# LoraModule.net
KiCad netlist of a schematic drawn in Altium Designer
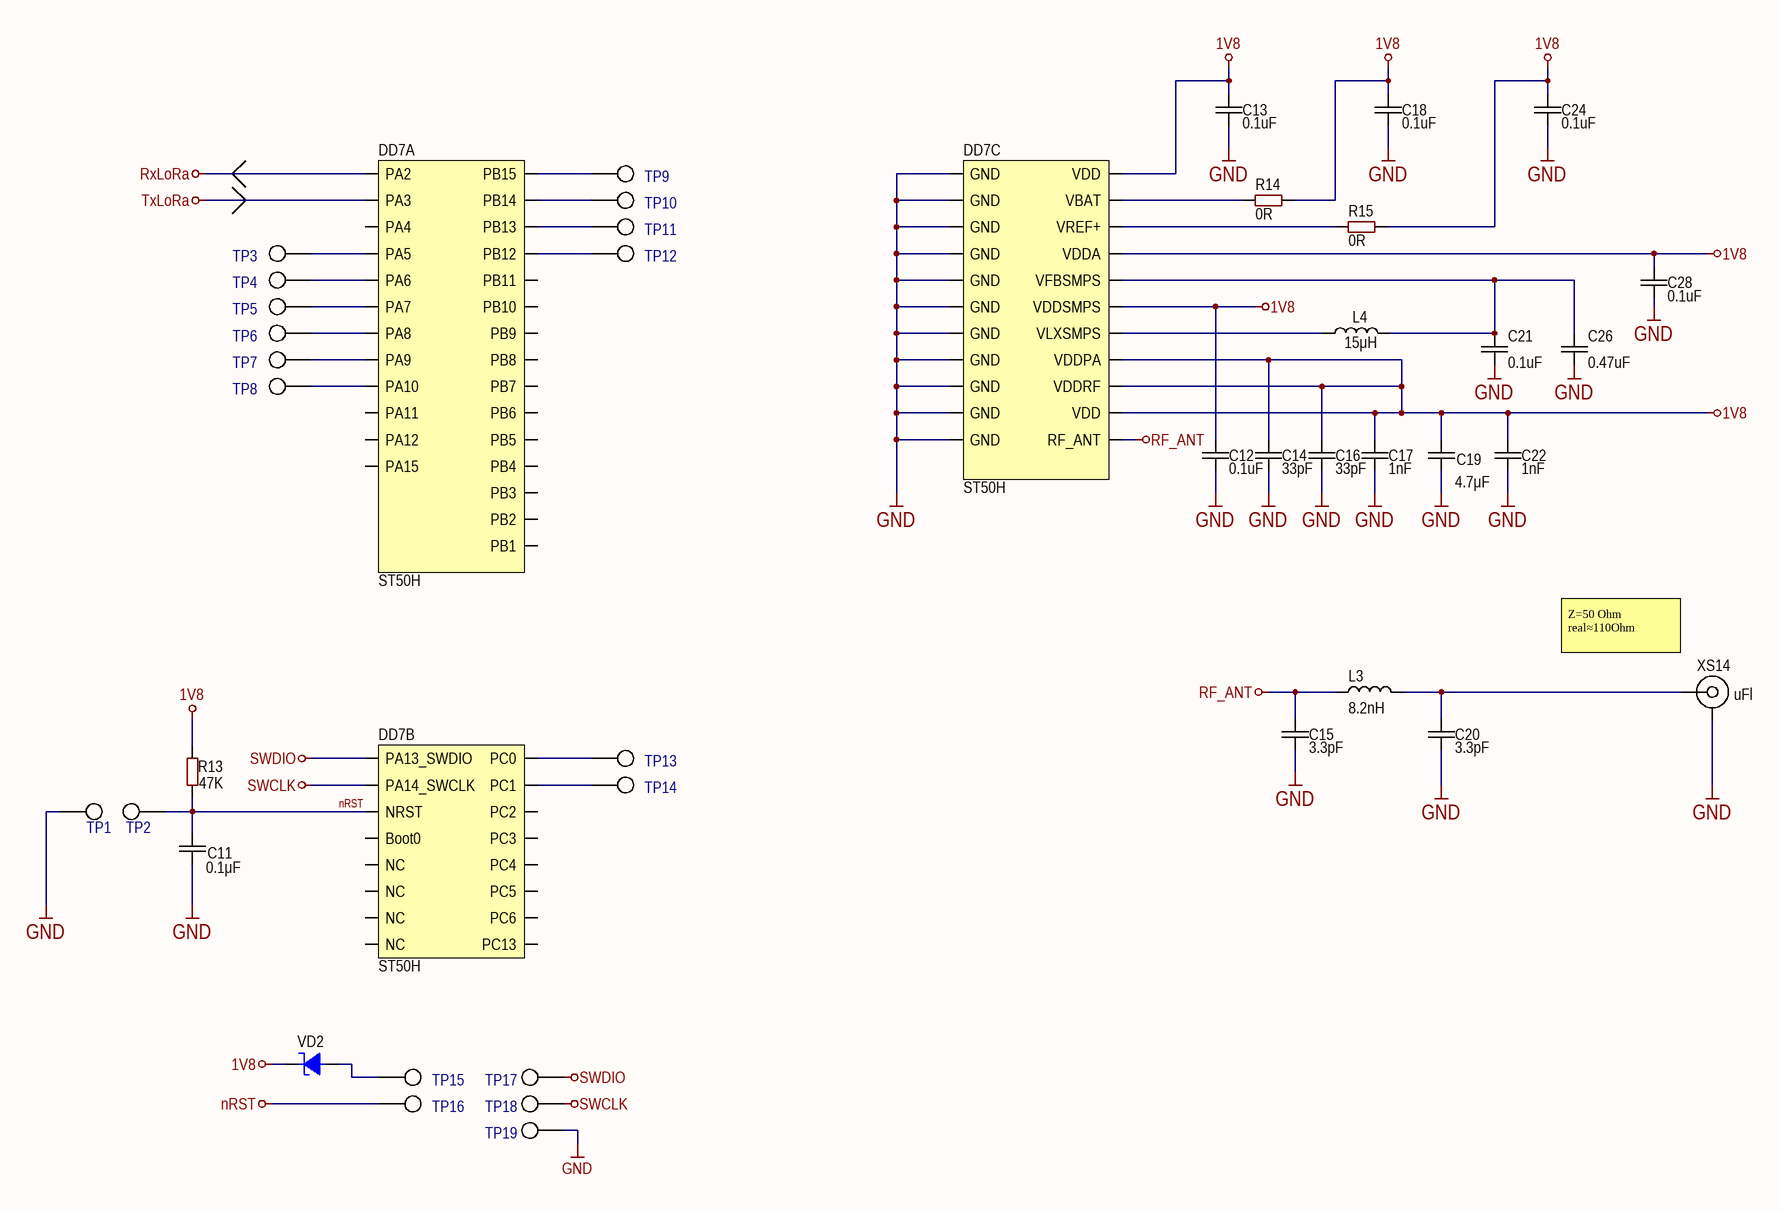
[diagram p0: LoraModule.SchDoc]

(export (version "E")
  (design (tool "Eeschema 10.0.6"))
  (components
    (comp (ref "C11")
      (value "0.1μF")
      (footprint "CAP: 0402")
      (fields
        (field (name "MANUFACTURER") "Yageo")
        (field (name "PARTNUMBER") "CC0402KRX7R7BB104")
        (field (name "VALUEMANUFACTURERPARTNUMBER") "Ceramic capacitor, 0.1μF, X7R, ±10%, 16V, 0402, -55...+125°C")
      )
      (libsource (lib "capacitor") (part "Ceramic_0402"))
    )
    (comp (ref "C12")
      (value "0.1uF")
      (footprint "CAP: 0402")
      (fields
        (field (name "MANUFACTURER") "Yageo")
        (field (name "PARTNUMBER") "CC0402KRX7R7BB104")
        (field (name "VALUEMANUFACTURERPARTNUMBER") "Ceramic capacitor, 0.1uF, X7R, ±10%, 16V, 0402, -55...+125°C")
      )
      (libsource (lib "capacitor") (part "Ceramic_0402"))
    )
    (comp (ref "C13")
      (value "0.1uF")
      (footprint "CAP: 0402")
      (fields
        (field (name "MANUFACTURER") "Yageo")
        (field (name "PARTNUMBER") "CC0402KRX7R7BB104")
        (field (name "VALUEMANUFACTURERPARTNUMBER") "Ceramic capacitor, 0.1uF, X7R, ±10%, 16V, 0402, -55...+125°C")
      )
      (libsource (lib "capacitor") (part "Ceramic_0402"))
    )
    (comp (ref "C14")
      (value "33pF")
      (footprint "CAP: 0402")
      (fields
        (field (name "MANUFACTURER") "Yageo")
        (field (name "PARTNUMBER") "CC0402KRX7R7BB104")
        (field (name "VALUEMANUFACTURERPARTNUMBER") "Ceramic capacitor, 33pF, X7R, ±10%, 16V, 0402, -55...+125°C")
      )
      (libsource (lib "capacitor") (part "Ceramic_0402"))
    )
    (comp (ref "C15")
      (value "3.3pF")
      (footprint "CAP: 0402")
      (fields
        (field (name "MANUFACTURER") "Yageo")
        (field (name "PARTNUMBER") "CC0402KRX7R7BB104")
        (field (name "VALUEMANUFACTURERPARTNUMBER") "Ceramic capacitor, 3.3pF, X7R, ±10%, 16V, 0402, -55...+125°C")
      )
      (libsource (lib "capacitor") (part "Ceramic_0402"))
    )
    (comp (ref "C16")
      (value "33pF")
      (footprint "CAP: 0402")
      (fields
        (field (name "MANUFACTURER") "Yageo")
        (field (name "PARTNUMBER") "CC0402KRX7R7BB104")
        (field (name "VALUEMANUFACTURERPARTNUMBER") "Ceramic capacitor, 33pF, X7R, ±10%, 16V, 0402, -55...+125°C")
      )
      (libsource (lib "capacitor") (part "Ceramic_0402"))
    )
    (comp (ref "C17")
      (value "1nF")
      (footprint "CAP: 0402")
      (fields
        (field (name "MANUFACTURER") "Yageo")
        (field (name "PARTNUMBER") "CC0402KRX7R7BB104")
        (field (name "VALUEMANUFACTURERPARTNUMBER") "Ceramic capacitor, 1nF, X7R, ±10%, 16V, 0402, -55...+125°C")
      )
      (libsource (lib "capacitor") (part "Ceramic_0402"))
    )
    (comp (ref "C18")
      (value "0.1uF")
      (footprint "CAP: 0402")
      (fields
        (field (name "MANUFACTURER") "Yageo")
        (field (name "PARTNUMBER") "CC0402KRX7R7BB104")
        (field (name "VALUEMANUFACTURERPARTNUMBER") "Ceramic capacitor, 0.1uF, X7R, ±10%, 16V, 0402, -55...+125°C")
      )
      (libsource (lib "capacitor") (part "Ceramic_0402"))
    )
    (comp (ref "C19")
      (value "4.7μF")
      (footprint "CAP: 0603")
      (fields
        (field (name "MANUFACTURER") "Yageo")
        (field (name "PARTNUMBER") "CC0603KRX7R7BB104")
        (field (name "VALUEMANUFACTURERPARTNUMBER") "Ceramic capacitor, 4.7μF, X7R, ±10%, 16V, 0603, -55...+125°C")
      )
      (libsource (lib "capacitor") (part "Ceramic_0603"))
    )
    (comp (ref "C20")
      (value "3.3pF")
      (footprint "CAP: 0402")
      (fields
        (field (name "MANUFACTURER") "Yageo")
        (field (name "PARTNUMBER") "CC0402KRX7R7BB104")
        (field (name "VALUEMANUFACTURERPARTNUMBER") "Ceramic capacitor, 3.3pF, X7R, ±10%, 16V, 0402, -55...+125°C")
      )
      (libsource (lib "capacitor") (part "Ceramic_0402"))
    )
    (comp (ref "C21")
      (value "0.1uF")
      (footprint "CAP: 0402")
      (fields
        (field (name "MANUFACTURER") "Yageo")
        (field (name "PARTNUMBER") "CC0402KRX7R7BB104")
        (field (name "VALUEMANUFACTURERPARTNUMBER") "Ceramic capacitor, 0.1uF, X7R, ±10%, 16V, 0402, -55...+125°C")
      )
      (libsource (lib "capacitor") (part "Ceramic_0402"))
    )
    (comp (ref "C22")
      (value "1nF")
      (footprint "CAP: 0402")
      (fields
        (field (name "MANUFACTURER") "Yageo")
        (field (name "PARTNUMBER") "CC0402KRX7R7BB104")
        (field (name "VALUEMANUFACTURERPARTNUMBER") "Ceramic capacitor, 1nF, X7R, ±10%, 16V, 0402, -55...+125°C")
      )
      (libsource (lib "capacitor") (part "Ceramic_0402"))
    )
    (comp (ref "C24")
      (value "0.1uF")
      (footprint "CAP: 0402")
      (fields
        (field (name "MANUFACTURER") "Yageo")
        (field (name "PARTNUMBER") "CC0402KRX7R7BB104")
        (field (name "VALUEMANUFACTURERPARTNUMBER") "Ceramic capacitor, 0.1uF, X7R, ±10%, 16V, 0402, -55...+125°C")
      )
      (libsource (lib "capacitor") (part "Ceramic_0402"))
    )
    (comp (ref "C26")
      (value "0.47uF")
      (footprint "CAP: 0402")
      (fields
        (field (name "MANUFACTURER") "Yageo")
        (field (name "PARTNUMBER") "CC0402KRX7R7BB104")
        (field (name "VALUEMANUFACTURERPARTNUMBER") "Ceramic capacitor, 0.47uF, X7R, ±10%, 16V, 0402, -55...+125°C")
      )
      (libsource (lib "capacitor") (part "Ceramic_0402"))
    )
    (comp (ref "C28")
      (value "0.1uF")
      (footprint "CAP: 0402")
      (fields
        (field (name "MANUFACTURER") "Yageo")
        (field (name "PARTNUMBER") "CC0402KRX7R7BB104")
        (field (name "VALUEMANUFACTURERPARTNUMBER") "Ceramic capacitor, 0.1uF, X7R, ±10%, 16V, 0402, -55...+125°C")
      )
      (libsource (lib "capacitor") (part "Ceramic_0402"))
    )
    (comp (ref "DD7")
      (value "ST50H")
      (footprint "ST50H")
      (description "LoRa module")
      (libsource (lib "ic-rf-transceiver") (part "ST50H"))
    )
    (comp (ref "L3")
      (value "8.2nH")
      (footprint "IND: 0402")
      (fields
        (field (name "MANUFACTURER") "Murata Electronics")
        (field (name "PARTNUMBER") "LQG15HSR10J02D")
        (field (name "VALUEMANUFACTURERPARTNUMBER") "Fixed inductor, 8.2nH, ±5%, 0402, 200mA, -55...+125°C")
      )
      (libsource (lib "inductor") (part "Inductor_0402"))
    )
    (comp (ref "L4")
      (value "15μH")
      (footprint "IND: 0805")
      (fields
        (field (name "MANUFACTURER") "Murata Electronics")
        (field (name "PARTNUMBER") "LQM21FN100M70L")
        (field (name "VALUEMANUFACTURERPARTNUMBER") "Fixed inductor, 15μH, ±20%, 0805, 100mA, -55...+125°C")
      )
      (libsource (lib "inductor") (part "Inductor_0805"))
    )
    (comp (ref "R13")
      (value "47K")
      (footprint "RES: 0402")
      (fields
        (field (name "MANUFACTURER") "Yageo")
        (field (name "PARTNUMBER") "RC0402JR-07100RL")
        (field (name "VALUEMANUFACTURERPARTNUMBER") "Resistor film, 47K, ±5%, 0402, 0.063W, -55...+125°C")
      )
      (libsource (lib "") (part "Resistor_0402_1"))
    )
    (comp (ref "R14")
      (value "0R")
      (footprint "RES: 0402")
      (fields
        (field (name "MANUFACTURER") "Yageo")
        (field (name "PARTNUMBER") "RC0402JR-07100RL")
        (field (name "VALUEMANUFACTURERPARTNUMBER") "Resistor film, 0R, ±5%, 0402, 0.063W, -55...+125°C")
      )
      (libsource (lib "resistor") (part "Resistor_0402"))
    )
    (comp (ref "R15")
      (value "0R")
      (footprint "RES: 0402")
      (fields
        (field (name "MANUFACTURER") "Yageo")
        (field (name "PARTNUMBER") "RC0402JR-07100RL")
        (field (name "VALUEMANUFACTURERPARTNUMBER") "Resistor film, 0R, ±5%, 0402, 0.063W, -55...+125°C")
      )
      (libsource (lib "resistor") (part "Resistor_0402"))
    )
    (comp (ref "TP1")
      (value "Testpoint_HS1mm")
      (footprint "TestPoint(without 3D)")
      (libsource (lib "connector") (part "Testpoint_HS1mm"))
    )
    (comp (ref "TP2")
      (value "Testpoint_HS1mm")
      (footprint "TestPoint(without 3D)")
      (libsource (lib "connector") (part "Testpoint_HS1mm"))
    )
    (comp (ref "TP3")
      (value "Testpoint_HS1mm")
      (footprint "TestPoint(without hole)")
      (libsource (lib "connector") (part "Testpoint_HS1mm"))
    )
    (comp (ref "TP4")
      (value "Testpoint_HS1mm")
      (footprint "TestPoint(without hole)")
      (libsource (lib "connector") (part "Testpoint_HS1mm"))
    )
    (comp (ref "TP5")
      (value "Testpoint_HS1mm")
      (footprint "TestPoint(without hole)")
      (libsource (lib "connector") (part "Testpoint_HS1mm"))
    )
    (comp (ref "TP6")
      (value "Testpoint_HS1mm")
      (footprint "TestPoint(without hole)")
      (libsource (lib "connector") (part "Testpoint_HS1mm"))
    )
    (comp (ref "TP7")
      (value "Testpoint_HS1mm")
      (footprint "TestPoint(without hole)")
      (libsource (lib "connector") (part "Testpoint_HS1mm"))
    )
    (comp (ref "TP8")
      (value "Testpoint_HS1mm")
      (footprint "TestPoint(without hole)")
      (libsource (lib "connector") (part "Testpoint_HS1mm"))
    )
    (comp (ref "TP9")
      (value "Testpoint_HS1mm")
      (footprint "TestPoint(without hole)")
      (libsource (lib "connector") (part "Testpoint_HS1mm"))
    )
    (comp (ref "TP10")
      (value "Testpoint_HS1mm")
      (footprint "TestPoint(without hole)")
      (libsource (lib "connector") (part "Testpoint_HS1mm"))
    )
    (comp (ref "TP11")
      (value "Testpoint_HS1mm")
      (footprint "TestPoint(without hole)")
      (libsource (lib "connector") (part "Testpoint_HS1mm"))
    )
    (comp (ref "TP12")
      (value "Testpoint_HS1mm")
      (footprint "TestPoint(without hole)")
      (libsource (lib "connector") (part "Testpoint_HS1mm"))
    )
    (comp (ref "TP13")
      (value "Testpoint_HS1mm")
      (footprint "TestPoint(without hole)")
      (libsource (lib "connector") (part "Testpoint_HS1mm"))
    )
    (comp (ref "TP14")
      (value "Testpoint_HS1mm")
      (footprint "TestPoint(without hole)")
      (libsource (lib "connector") (part "Testpoint_HS1mm"))
    )
    (comp (ref "TP15")
      (value "Testpoint_HS1mm")
      (footprint "TestPoint(without hole)")
      (libsource (lib "connector") (part "Testpoint_HS1mm"))
    )
    (comp (ref "TP16")
      (value "Testpoint_HS1mm")
      (footprint "TestPoint(without hole)")
      (libsource (lib "connector") (part "Testpoint_HS1mm"))
    )
    (comp (ref "TP17")
      (value "Testpoint_HS1mm")
      (footprint "TestPoint(without hole)")
      (libsource (lib "connector") (part "Testpoint_HS1mm"))
    )
    (comp (ref "TP18")
      (value "Testpoint_HS1mm")
      (footprint "TestPoint(without hole)")
      (libsource (lib "connector") (part "Testpoint_HS1mm"))
    )
    (comp (ref "TP19")
      (value "Testpoint_HS1mm")
      (footprint "TestPoint(without hole)")
      (libsource (lib "connector") (part "Testpoint_HS1mm"))
    )
    (comp (ref "VD2")
      (value "~")
      (footprint "DIODE: SOD523")
      (fields
        (field (name "MANUFACTURER") "Diodes Incorporated")
        (field (name "VALUEMANUFACTURERPARTNUMBER") "Schottky diode, 80V, 500mA, 1V, 15pF, SOD-123, -55...+150°C")
        (field (name "VOLTAGE") "80V")
      )
      (libsource (lib "diode") (part "Schottky_single"))
    )
    (comp (ref "XS14")
      (value "~")
      (footprint "CON: u.Fl")
      (fields
        (field (name "MANUFACTURER") "Hirose Electric")
        (field (name "VALUEMANUFACTURERPARTNUMBER") "Connector u.FL, 50 Ohm, 6GHz")
        (field (name "PARTNUMBER") "U.FL-R-SMT(01)")
        (field (name "COMMENTTEXT") "uFl")
      )
      (libsource (lib "connector") (part "Connector_uFL"))
    )
  )
  (nets
    (net (code "1") (name "1V8") (class "Default")
      (node (ref "C12") (pin "2") (pinfunction "2_2") (pintype "passive"))
      (node (ref "C13") (pin "2") (pinfunction "2_2") (pintype "passive"))
      (node (ref "C14") (pin "2") (pinfunction "2_2") (pintype "passive"))
      (node (ref "C16") (pin "2") (pinfunction "2_2") (pintype "passive"))
      (node (ref "C17") (pin "2") (pinfunction "2_2") (pintype "passive"))
      (node (ref "C18") (pin "2") (pinfunction "2_2") (pintype "passive"))
      (node (ref "C19") (pin "2") (pinfunction "2_2") (pintype "passive"))
      (node (ref "C22") (pin "2") (pinfunction "2_2") (pintype "passive"))
      (node (ref "C24") (pin "2") (pinfunction "2_2") (pintype "passive"))
      (node (ref "C28") (pin "2") (pinfunction "2_2") (pintype "passive"))
      (node (ref "DD7") (pin "11") (pinfunction "VDDSMPS_11") (pintype "passive"))
      (node (ref "DD7") (pin "3") (pinfunction "VDD_3") (pintype "passive"))
      (node (ref "DD7") (pin "53") (pinfunction "VDDPA_53") (pintype "passive"))
      (node (ref "DD7") (pin "54") (pinfunction "VDDRF_54") (pintype "passive"))
      (node (ref "DD7") (pin "55") (pinfunction "VDD_55") (pintype "passive"))
      (node (ref "DD7") (pin "7") (pinfunction "VDDA_7") (pintype "passive"))
      (node (ref "R13") (pin "2") (pinfunction "2_2") (pintype "passive"))
      (node (ref "R14") (pin "1") (pinfunction "1_1") (pintype "passive"))
      (node (ref "R15") (pin "1") (pinfunction "1_1") (pintype "passive"))
      (node (ref "VD2") (pin "2") (pinfunction "2_2") (pintype "passive"))
    )
    (net (code "2") (name "GND") (class "Default")
      (node (ref "C11") (pin "1") (pinfunction "1_1") (pintype "passive"))
      (node (ref "C12") (pin "1") (pinfunction "1_1") (pintype "passive"))
      (node (ref "C13") (pin "1") (pinfunction "1_1") (pintype "passive"))
      (node (ref "C14") (pin "1") (pinfunction "1_1") (pintype "passive"))
      (node (ref "C15") (pin "1") (pinfunction "1_1") (pintype "passive"))
      (node (ref "C16") (pin "1") (pinfunction "1_1") (pintype "passive"))
      (node (ref "C17") (pin "1") (pinfunction "1_1") (pintype "passive"))
      (node (ref "C18") (pin "1") (pinfunction "1_1") (pintype "passive"))
      (node (ref "C19") (pin "1") (pinfunction "1_1") (pintype "passive"))
      (node (ref "C20") (pin "1") (pinfunction "1_1") (pintype "passive"))
      (node (ref "C21") (pin "1") (pinfunction "1_1") (pintype "passive"))
      (node (ref "C22") (pin "1") (pinfunction "1_1") (pintype "passive"))
      (node (ref "C24") (pin "1") (pinfunction "1_1") (pintype "passive"))
      (node (ref "C26") (pin "2") (pinfunction "2_2") (pintype "passive"))
      (node (ref "C28") (pin "1") (pinfunction "1_1") (pintype "passive"))
      (node (ref "DD7") (pin "12") (pinfunction "GND_12") (pintype "passive"))
      (node (ref "DD7") (pin "28") (pinfunction "GND_28") (pintype "passive"))
      (node (ref "DD7") (pin "35") (pinfunction "GND_35") (pintype "passive"))
      (node (ref "DD7") (pin "36") (pinfunction "GND_36") (pintype "passive"))
      (node (ref "DD7") (pin "38") (pinfunction "GND_38") (pintype "passive"))
      (node (ref "DD7") (pin "39") (pinfunction "GND_39") (pintype "passive"))
      (node (ref "DD7") (pin "46") (pinfunction "GND_46") (pintype "passive"))
      (node (ref "DD7") (pin "47") (pinfunction "GND_47") (pintype "passive"))
      (node (ref "DD7") (pin "52") (pinfunction "GND_52") (pintype "passive"))
      (node (ref "DD7") (pin "56") (pinfunction "GND_56") (pintype "passive"))
      (node (ref "DD7") (pin "65") (pinfunction "GND_65") (pintype "passive"))
      (node (ref "TP1") (pin "1") (pinfunction "1_1") (pintype "passive"))
      (node (ref "TP19") (pin "1") (pinfunction "1_1") (pintype "passive"))
      (node (ref "XS14") (pin "2") (pinfunction "2_2") (pintype "passive"))
    )
    (net (code "3") (name "Net-(C20-Pad2)") (class "Default")
      (node (ref "C20") (pin "2") (pinfunction "2_2") (pintype "passive"))
      (node (ref "L3") (pin "2") (pinfunction "2_2") (pintype "passive"))
      (node (ref "XS14") (pin "1") (pinfunction "1_1") (pintype "passive"))
    )
    (net (code "4") (name "Net-(DD7A-PA5)") (class "Default")
      (node (ref "DD7") (pin "32") (pinfunction "PA5_32") (pintype "passive"))
      (node (ref "TP3") (pin "1") (pinfunction "1_1") (pintype "passive"))
    )
    (net (code "5") (name "Net-(DD7A-PA6)") (class "Default")
      (node (ref "DD7") (pin "33") (pinfunction "PA6_33") (pintype "passive"))
      (node (ref "TP4") (pin "1") (pinfunction "1_1") (pintype "passive"))
    )
    (net (code "6") (name "Net-(DD7A-PA7)") (class "Default")
      (node (ref "DD7") (pin "34") (pinfunction "PA7_34") (pintype "passive"))
      (node (ref "TP5") (pin "1") (pinfunction "1_1") (pintype "passive"))
    )
    (net (code "7") (name "Net-(DD7A-PA8)") (class "Default")
      (node (ref "DD7") (pin "51") (pinfunction "PA8_51") (pintype "passive"))
      (node (ref "TP6") (pin "1") (pinfunction "1_1") (pintype "passive"))
    )
    (net (code "8") (name "Net-(DD7A-PA9)") (class "Default")
      (node (ref "DD7") (pin "50") (pinfunction "PA9_50") (pintype "passive"))
      (node (ref "TP7") (pin "1") (pinfunction "1_1") (pintype "passive"))
    )
    (net (code "9") (name "Net-(DD7A-PA10)") (class "Default")
      (node (ref "DD7") (pin "62") (pinfunction "PA10_62") (pintype "passive"))
      (node (ref "TP8") (pin "1") (pinfunction "1_1") (pintype "passive"))
    )
    (net (code "10") (name "Net-(DD7A-PB12)") (class "Default")
      (node (ref "DD7") (pin "59") (pinfunction "PB12_59") (pintype "passive"))
      (node (ref "TP12") (pin "1") (pinfunction "1_1") (pintype "passive"))
    )
    (net (code "11") (name "Net-(DD7A-PB13)") (class "Default")
      (node (ref "DD7") (pin "60") (pinfunction "PB13_60") (pintype "passive"))
      (node (ref "TP11") (pin "1") (pinfunction "1_1") (pintype "passive"))
    )
    (net (code "12") (name "Net-(DD7A-PB14)") (class "Default")
      (node (ref "DD7") (pin "61") (pinfunction "PB14_61") (pintype "passive"))
      (node (ref "TP10") (pin "1") (pinfunction "1_1") (pintype "passive"))
    )
    (net (code "13") (name "Net-(DD7A-PB15)") (class "Default")
      (node (ref "DD7") (pin "9") (pinfunction "PB15_9") (pintype "passive"))
      (node (ref "TP9") (pin "1") (pinfunction "1_1") (pintype "passive"))
    )
    (net (code "14") (name "Net-(DD7B-PC0)") (class "Default")
      (node (ref "DD7") (pin "21") (pinfunction "PC0_21") (pintype "passive"))
      (node (ref "TP13") (pin "1") (pinfunction "1_1") (pintype "passive"))
    )
    (net (code "15") (name "Net-(DD7B-PC1)") (class "Default")
      (node (ref "DD7") (pin "22") (pinfunction "PC1_22") (pintype "passive"))
      (node (ref "TP14") (pin "1") (pinfunction "1_1") (pintype "passive"))
    )
    (net (code "16") (name "Net-(DD7C-VBAT)") (class "Default")
      (node (ref "DD7") (pin "4") (pinfunction "VBAT_4") (pintype "passive"))
      (node (ref "R14") (pin "2") (pinfunction "2_2") (pintype "passive"))
    )
    (net (code "17") (name "Net-(DD7C-VFBSMPS)") (class "Default")
      (node (ref "C21") (pin "2") (pinfunction "2_2") (pintype "passive"))
      (node (ref "C26") (pin "1") (pinfunction "1_1") (pintype "passive"))
      (node (ref "DD7") (pin "10") (pinfunction "VFBSMPS_10") (pintype "passive"))
      (node (ref "L4") (pin "2") (pinfunction "2_2") (pintype "passive"))
    )
    (net (code "18") (name "Net-(DD7C-VLXSMPS)") (class "Default")
      (node (ref "DD7") (pin "13") (pinfunction "VLXSMPS_13") (pintype "passive"))
      (node (ref "L4") (pin "1") (pinfunction "1_1") (pintype "passive"))
    )
    (net (code "19") (name "Net-(DD7C-VREF+)") (class "Default")
      (node (ref "DD7") (pin "6") (pinfunction "VREF+_6") (pintype "passive"))
      (node (ref "R15") (pin "2") (pinfunction "2_2") (pintype "passive"))
    )
    (net (code "20") (name "Net-(TP15-Pad1)") (class "Default")
      (node (ref "TP15") (pin "1") (pinfunction "1_1") (pintype "passive"))
      (node (ref "VD2") (pin "1") (pinfunction "1_1") (pintype "passive"))
    )
    (net (code "21") (name "RF_ANT") (class "Default")
      (node (ref "C15") (pin "2") (pinfunction "2_2") (pintype "passive"))
      (node (ref "DD7") (pin "37") (pinfunction "RF_ANT_37") (pintype "passive"))
      (node (ref "L3") (pin "1") (pinfunction "1_1") (pintype "passive"))
    )
    (net (code "22") (name "RxLoRa") (class "Default")
      (node (ref "DD7") (pin "29") (pinfunction "PA2_29") (pintype "passive"))
    )
    (net (code "23") (name "SWCLK") (class "Default")
      (node (ref "DD7") (pin "2") (pinfunction "PA14_SWCLK_2") (pintype "passive"))
      (node (ref "TP18") (pin "1") (pinfunction "1_1") (pintype "passive"))
    )
    (net (code "24") (name "SWDIO") (class "Default")
      (node (ref "DD7") (pin "1") (pinfunction "PA13_SWDIO_1") (pintype "passive"))
      (node (ref "TP17") (pin "1") (pinfunction "1_1") (pintype "passive"))
    )
    (net (code "25") (name "TxLoRa") (class "Default")
      (node (ref "DD7") (pin "30") (pinfunction "PA3_30") (pintype "passive"))
    )
    (net (code "26") (name "nRST") (class "Default")
      (node (ref "C11") (pin "2") (pinfunction "2_2") (pintype "passive"))
      (node (ref "DD7") (pin "44") (pinfunction "NRST_44") (pintype "passive"))
      (node (ref "R13") (pin "1") (pinfunction "1_1") (pintype "passive"))
      (node (ref "TP16") (pin "1") (pinfunction "1_1") (pintype "passive"))
      (node (ref "TP2") (pin "1") (pinfunction "1_1") (pintype "passive"))
    )
    (net (code "27") (name "unconnected-(DD7A-PA4-Pad31)") (class "Default")
      (node (ref "DD7") (pin "31") (pinfunction "PA4_31") (pintype "passive"))
    )
    (net (code "28") (name "unconnected-(DD7A-PA11-Pad63)") (class "Default")
      (node (ref "DD7") (pin "63") (pinfunction "PA11_63") (pintype "passive"))
    )
    (net (code "29") (name "unconnected-(DD7A-PA12-Pad64)") (class "Default")
      (node (ref "DD7") (pin "64") (pinfunction "PA12_64") (pintype "passive"))
    )
    (net (code "30") (name "unconnected-(DD7A-PA15-Pad8)") (class "Default")
      (node (ref "DD7") (pin "8") (pinfunction "PA15_8") (pintype "passive"))
    )
    (net (code "31") (name "unconnected-(DD7A-PB1-Pad57)") (class "Default")
      (node (ref "DD7") (pin "57") (pinfunction "PB1_57") (pintype "passive"))
    )
    (net (code "32") (name "unconnected-(DD7A-PB2-Pad58)") (class "Default")
      (node (ref "DD7") (pin "58") (pinfunction "PB2_58") (pintype "passive"))
    )
    (net (code "33") (name "unconnected-(DD7A-PB3-Pad14)") (class "Default")
      (node (ref "DD7") (pin "14") (pinfunction "PB3_14") (pintype "passive"))
    )
    (net (code "34") (name "unconnected-(DD7A-PB4-Pad15)") (class "Default")
      (node (ref "DD7") (pin "15") (pinfunction "PB4_15") (pintype "passive"))
    )
    (net (code "35") (name "unconnected-(DD7A-PB5-Pad16)") (class "Default")
      (node (ref "DD7") (pin "16") (pinfunction "PB5_16") (pintype "passive"))
    )
    (net (code "36") (name "unconnected-(DD7A-PB6-Pad17)") (class "Default")
      (node (ref "DD7") (pin "17") (pinfunction "PB6_17") (pintype "passive"))
    )
    (net (code "37") (name "unconnected-(DD7A-PB7-Pad18)") (class "Default")
      (node (ref "DD7") (pin "18") (pinfunction "PB7_18") (pintype "passive"))
    )
    (net (code "38") (name "unconnected-(DD7A-PB8-Pad19)") (class "Default")
      (node (ref "DD7") (pin "19") (pinfunction "PB8_19") (pintype "passive"))
    )
    (net (code "39") (name "unconnected-(DD7A-PB9-Pad20)") (class "Default")
      (node (ref "DD7") (pin "20") (pinfunction "PB9_20") (pintype "passive"))
    )
    (net (code "40") (name "unconnected-(DD7A-PB10-Pad49)") (class "Default")
      (node (ref "DD7") (pin "49") (pinfunction "PB10_49") (pintype "passive"))
    )
    (net (code "41") (name "unconnected-(DD7A-PB11-Pad48)") (class "Default")
      (node (ref "DD7") (pin "48") (pinfunction "PB11_48") (pintype "passive"))
    )
    (net (code "42") (name "unconnected-(DD7B-Boot0-Pad43)") (class "Default")
      (node (ref "DD7") (pin "43") (pinfunction "Boot0_43") (pintype "passive"))
    )
    (net (code "43") (name "unconnected-(DD7B-NC-Pad40)") (class "Default")
      (node (ref "DD7") (pin "40") (pinfunction "NC_40") (pintype "passive"))
    )
    (net (code "44") (name "unconnected-(DD7B-NC-Pad41)") (class "Default")
      (node (ref "DD7") (pin "41") (pinfunction "NC_41") (pintype "passive"))
    )
    (net (code "45") (name "unconnected-(DD7B-NC-Pad42)") (class "Default")
      (node (ref "DD7") (pin "42") (pinfunction "NC_42") (pintype "passive"))
    )
    (net (code "46") (name "unconnected-(DD7B-NC-Pad45)") (class "Default")
      (node (ref "DD7") (pin "45") (pinfunction "NC_45") (pintype "passive"))
    )
    (net (code "47") (name "unconnected-(DD7B-PC2-Pad23)") (class "Default")
      (node (ref "DD7") (pin "23") (pinfunction "PC2_23") (pintype "passive"))
    )
    (net (code "48") (name "unconnected-(DD7B-PC3-Pad24)") (class "Default")
      (node (ref "DD7") (pin "24") (pinfunction "PC3_24") (pintype "passive"))
    )
    (net (code "49") (name "unconnected-(DD7B-PC4-Pad25)") (class "Default")
      (node (ref "DD7") (pin "25") (pinfunction "PC4_25") (pintype "passive"))
    )
    (net (code "50") (name "unconnected-(DD7B-PC5-Pad26)") (class "Default")
      (node (ref "DD7") (pin "26") (pinfunction "PC5_26") (pintype "passive"))
    )
    (net (code "51") (name "unconnected-(DD7B-PC6-Pad27)") (class "Default")
      (node (ref "DD7") (pin "27") (pinfunction "PC6_27") (pintype "passive"))
    )
    (net (code "52") (name "unconnected-(DD7B-PC13-Pad5)") (class "Default")
      (node (ref "DD7") (pin "5") (pinfunction "PC13_5") (pintype "passive"))
    )
  )
)
